# BLDC.net
KiCad netlist of a schematic drawn in Altium Designer
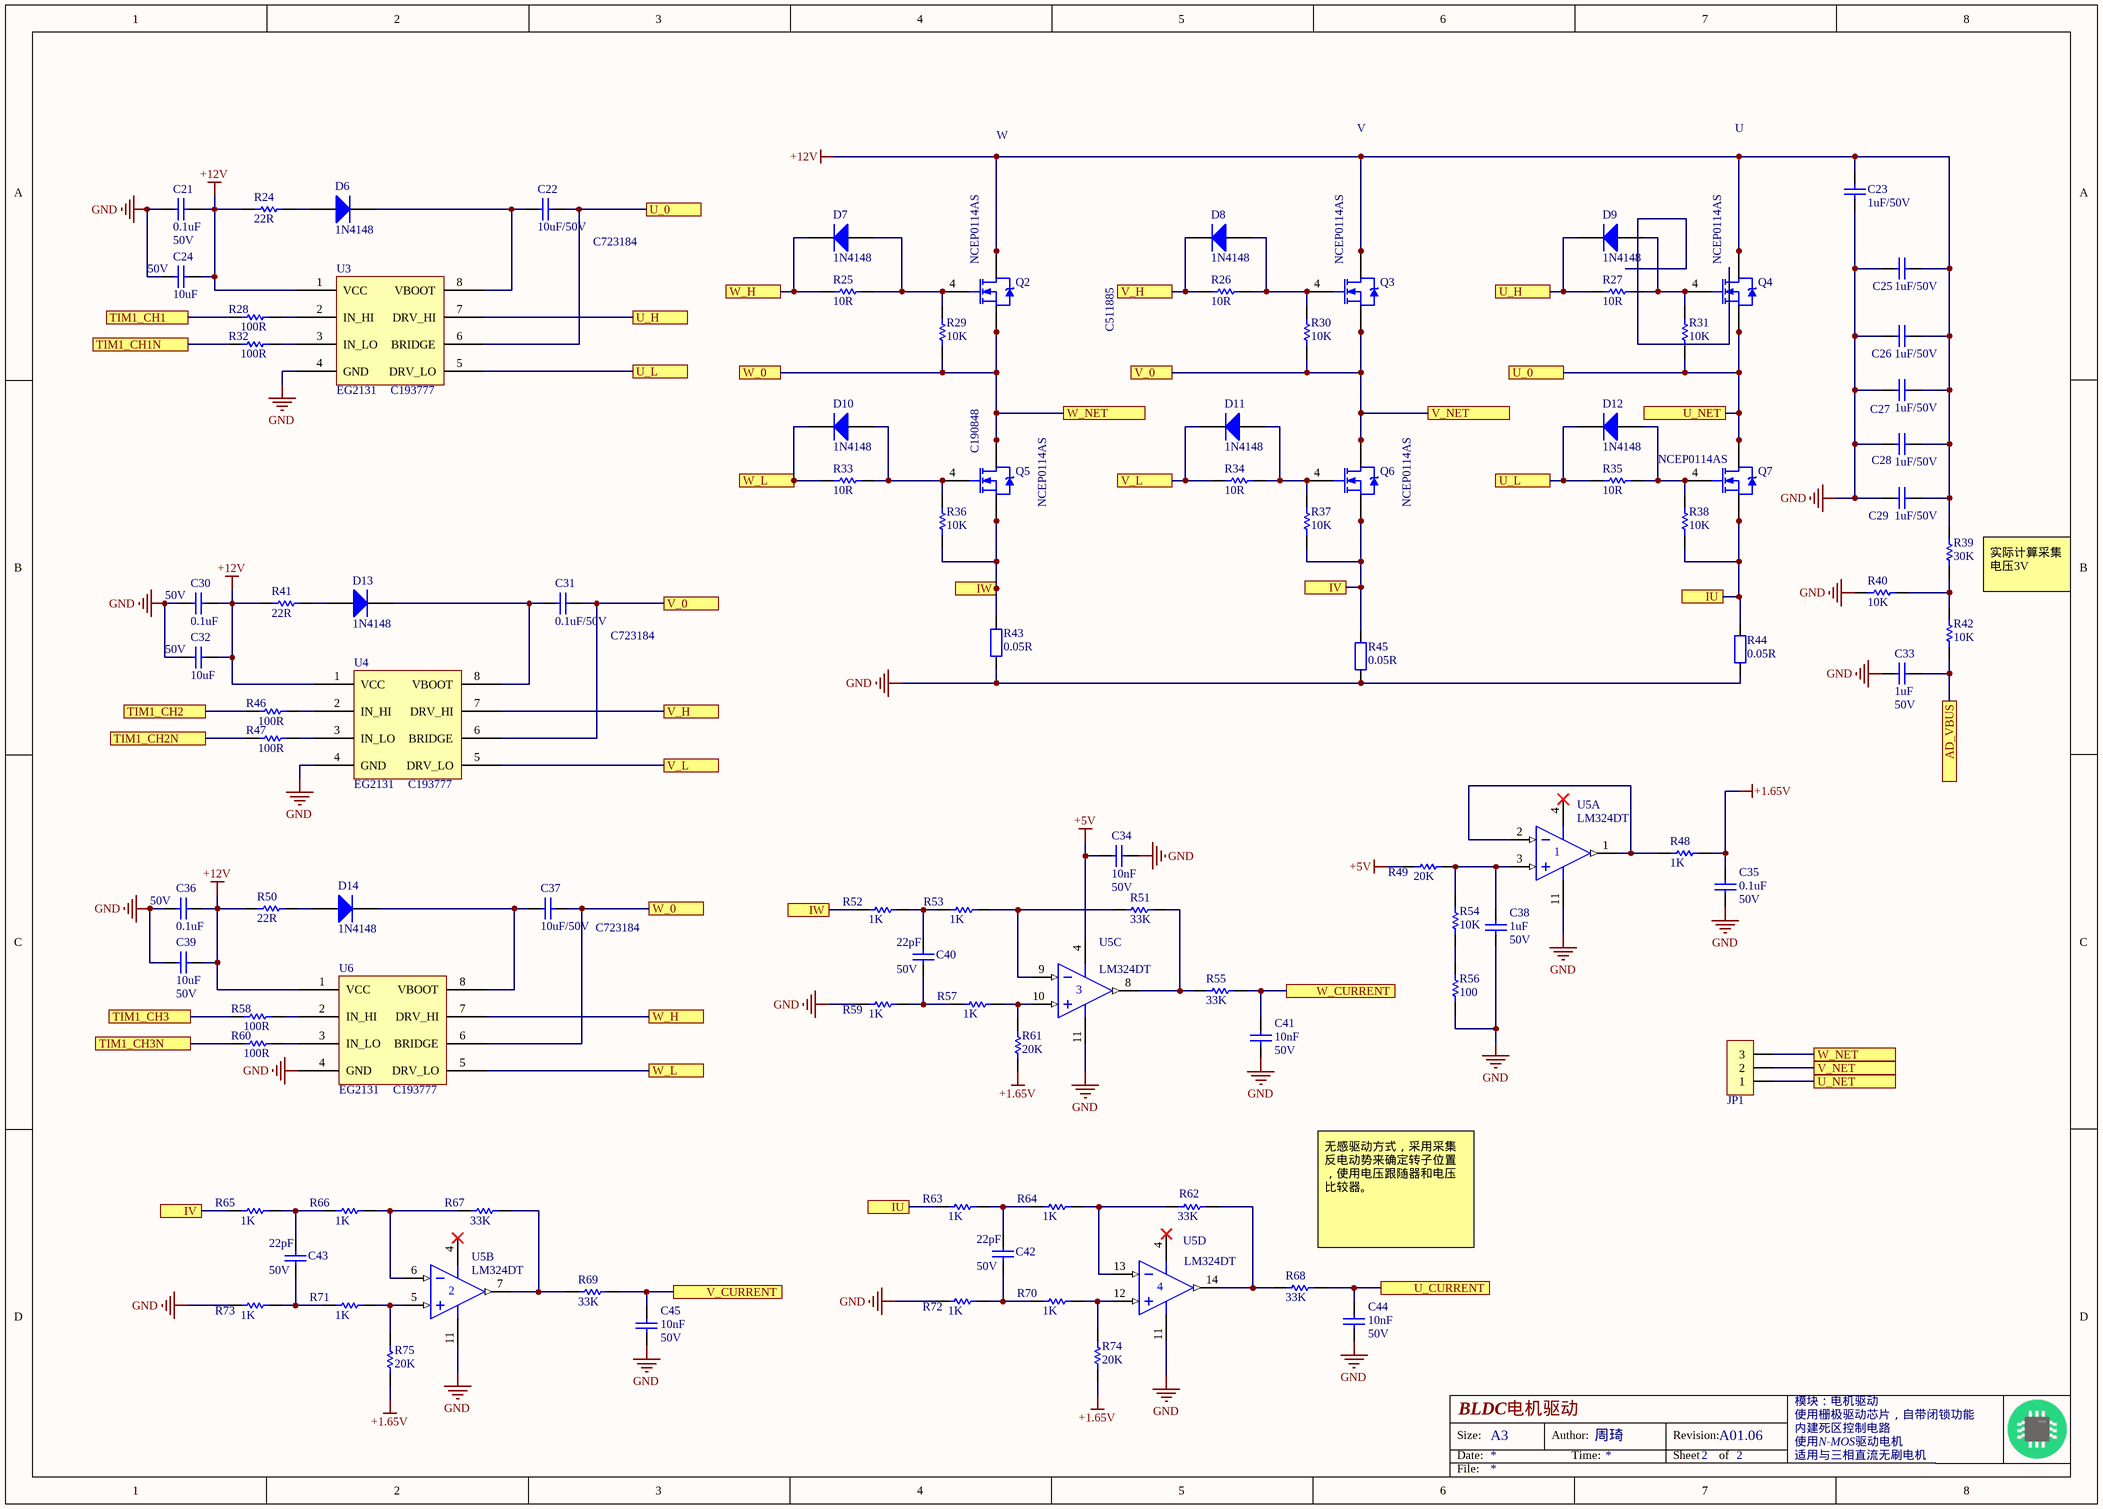
[diagram p0: BLDC.SchDoc]

(export (version "E")
  (design (tool "Eeschema 10.0.6"))
  (components
    (comp (ref "C21")
      (value "0.1uF")
      (footprint "C0603_L")
      (fields (field (name "PARM") "50V"))
      (libsource (lib "Miscellaneous Devices") (part "Cap"))
    )
    (comp (ref "C22")
      (value "10uF/50V")
      (footprint "C0603_L")
      (description "C89632")
      (libsource (lib "Miscellaneous Devices") (part "Cap"))
    )
    (comp (ref "C23")
      (value "1uF/50V")
      (footprint "C1210_L")
      (libsource (lib "Miscellaneous Devices") (part "Cap"))
    )
    (comp (ref "C24")
      (value "10uF")
      (footprint "C0805_L")
      (fields (field (name "PARM") "50V"))
      (libsource (lib "Miscellaneous Devices") (part "Cap"))
    )
    (comp (ref "C25")
      (value "1uF/50V")
      (footprint "C1210_L")
      (libsource (lib "Miscellaneous Devices") (part "Cap"))
    )
    (comp (ref "C26")
      (value "1uF/50V")
      (footprint "C1210_L")
      (libsource (lib "Miscellaneous Devices") (part "Cap"))
    )
    (comp (ref "C27")
      (value "1uF/50V")
      (footprint "C1210_L")
      (libsource (lib "Miscellaneous Devices") (part "Cap"))
    )
    (comp (ref "C28")
      (value "1uF/50V")
      (footprint "C1210_L")
      (libsource (lib "Miscellaneous Devices") (part "Cap"))
    )
    (comp (ref "C29")
      (value "1uF/50V")
      (footprint "C1210_L")
      (libsource (lib "Miscellaneous Devices") (part "Cap"))
    )
    (comp (ref "C30")
      (value "0.1uF")
      (footprint "C0603_L")
      (fields (field (name "PARM") "50V"))
      (libsource (lib "Miscellaneous Devices") (part "Cap"))
    )
    (comp (ref "C31")
      (value "0.1uF/50V")
      (footprint "C0603_L")
      (description "C89632")
      (libsource (lib "Miscellaneous Devices") (part "Cap"))
    )
    (comp (ref "C32")
      (value "10uF")
      (footprint "C0805_L")
      (fields (field (name "PARM") "50V"))
      (libsource (lib "Miscellaneous Devices") (part "Cap"))
    )
    (comp (ref "C33")
      (value "1uF")
      (footprint "C0603_L")
      (fields (field (name "PARM") "50V"))
      (libsource (lib "Miscellaneous Devices") (part "Cap"))
    )
    (comp (ref "C34")
      (value "10nF")
      (footprint "C0603_L")
      (fields (field (name "PARM") "50V"))
      (libsource (lib "Miscellaneous Devices") (part "Cap"))
    )
    (comp (ref "C35")
      (value "0.1uF")
      (footprint "C0603_L")
      (fields (field (name "PARM") "50V"))
      (libsource (lib "Miscellaneous Devices") (part "Cap"))
    )
    (comp (ref "C36")
      (value "0.1uF")
      (footprint "C0603_L")
      (fields (field (name "PARM") "50V"))
      (libsource (lib "Miscellaneous Devices") (part "Cap"))
    )
    (comp (ref "C37")
      (value "10uF/50V")
      (footprint "C0603_L")
      (description "C89632")
      (libsource (lib "Miscellaneous Devices") (part "Cap"))
    )
    (comp (ref "C38")
      (value "1uF")
      (footprint "C0603_L")
      (fields (field (name "PARM") "50V"))
      (libsource (lib "Miscellaneous Devices") (part "Cap"))
    )
    (comp (ref "C39")
      (value "10uF")
      (footprint "C0805_L")
      (fields (field (name "PARM") "50V"))
      (libsource (lib "Miscellaneous Devices") (part "Cap"))
    )
    (comp (ref "C40")
      (value "22pF")
      (footprint "C0603_L")
      (fields (field (name "PARM") "50V"))
      (libsource (lib "Miscellaneous Devices") (part "Cap"))
    )
    (comp (ref "C41")
      (value "10nF")
      (footprint "C0603_L")
      (fields (field (name "PARM") "50V"))
      (libsource (lib "Miscellaneous Devices") (part "Cap"))
    )
    (comp (ref "C42")
      (value "22pF")
      (footprint "C0603_L")
      (fields (field (name "PARM") "50V"))
      (libsource (lib "Miscellaneous Devices") (part "Cap"))
    )
    (comp (ref "C43")
      (value "22pF")
      (footprint "C0603_L")
      (fields (field (name "PARM") "50V"))
      (libsource (lib "Miscellaneous Devices") (part "Cap"))
    )
    (comp (ref "C44")
      (value "10nF")
      (footprint "C0603_L")
      (fields (field (name "PARM") "50V"))
      (libsource (lib "Miscellaneous Devices") (part "Cap"))
    )
    (comp (ref "C45")
      (value "10nF")
      (footprint "C0603_L")
      (fields (field (name "PARM") "50V"))
      (libsource (lib "Miscellaneous Devices") (part "Cap"))
    )
    (comp (ref "D6")
      (value "1N4148")
      (footprint "SOD-123")
      (description "二极管")
      (libsource (lib "Miscellaneous Devices LC") (part "SOD-323 1N4148WS T4"))
    )
    (comp (ref "D7")
      (value "1N4148")
      (footprint "SOD-123")
      (description "二极管")
      (libsource (lib "Miscellaneous Devices LC") (part "SOD-323 1N4148WS T4"))
    )
    (comp (ref "D8")
      (value "1N4148")
      (footprint "SOD-123")
      (description "二极管")
      (libsource (lib "Miscellaneous Devices LC") (part "SOD-323 1N4148WS T4"))
    )
    (comp (ref "D9")
      (value "1N4148")
      (footprint "SOD-123")
      (description "二极管")
      (libsource (lib "Miscellaneous Devices LC") (part "SOD-323 1N4148WS T4"))
    )
    (comp (ref "D10")
      (value "1N4148")
      (footprint "SOD-123")
      (description "二极管")
      (libsource (lib "Miscellaneous Devices LC") (part "SOD-323 1N4148WS T4"))
    )
    (comp (ref "D11")
      (value "1N4148")
      (footprint "SOD-123")
      (description "二极管")
      (libsource (lib "Miscellaneous Devices LC") (part "SOD-323 1N4148WS T4"))
    )
    (comp (ref "D12")
      (value "1N4148")
      (footprint "SOD-123")
      (description "二极管")
      (libsource (lib "Miscellaneous Devices LC") (part "SOD-323 1N4148WS T4"))
    )
    (comp (ref "D13")
      (value "1N4148")
      (footprint "SOD-123")
      (description "二极管")
      (libsource (lib "Miscellaneous Devices LC") (part "SOD-323 1N4148WS T4"))
    )
    (comp (ref "D14")
      (value "1N4148")
      (footprint "SOD-123")
      (description "二极管")
      (libsource (lib "Miscellaneous Devices LC") (part "SOD-323 1N4148WS T4"))
    )
    (comp (ref "JP1")
      (value "HDR-1X3")
      (footprint "KF350-3P")
      (description "3P接插件")
      (fields (field (name "版权归属") "源创客"))
      (libsource (lib "接插件") (part "Header 3"))
    )
    (comp (ref "Q2")
      (value "NCEP0114AS")
      (footprint "SOP8")
      (description "C190848")
      (fields (field (name "PUBLISHER") "60V"))
      (libsource (lib "Miscellaneous Devices") (part "NMOS-2"))
    )
    (comp (ref "Q3")
      (value "NCEP0114AS")
      (footprint "SOP8")
      (description "C190848")
      (fields (field (name "PUBLISHER") "60V"))
      (libsource (lib "Miscellaneous Devices") (part "NMOS-2"))
    )
    (comp (ref "Q4")
      (value "NCEP0114AS")
      (footprint "SOP8")
      (description "C190848")
      (fields (field (name "PUBLISHER") "60V"))
      (libsource (lib "Miscellaneous Devices") (part "NMOS-2"))
    )
    (comp (ref "Q5")
      (value "NCEP0114AS")
      (footprint "SOP8")
      (description "C190848")
      (fields (field (name "PUBLISHER") "60V"))
      (libsource (lib "Miscellaneous Devices") (part "NMOS-2"))
    )
    (comp (ref "Q6")
      (value "NCEP0114AS")
      (footprint "SOP8")
      (description "C190848")
      (fields (field (name "PUBLISHER") "60V"))
      (libsource (lib "Miscellaneous Devices") (part "NMOS-2"))
    )
    (comp (ref "Q7")
      (value "NCEP0114AS")
      (footprint "SOP8")
      (description "C190848")
      (fields (field (name "PUBLISHER") "60V"))
      (libsource (lib "Miscellaneous Devices") (part "NMOS-2"))
    )
    (comp (ref "R24")
      (value "22R")
      (footprint "R0603_L")
      (description "Resistor")
      (libsource (lib "Miscellaneous Devices") (part "Res1"))
    )
    (comp (ref "R25")
      (value "10R")
      (footprint "R0603_L")
      (description "Resistor")
      (libsource (lib "Miscellaneous Devices") (part "Res1"))
    )
    (comp (ref "R26")
      (value "10R")
      (footprint "R0603_L")
      (description "Resistor")
      (libsource (lib "Miscellaneous Devices") (part "Res1"))
    )
    (comp (ref "R27")
      (value "10R")
      (footprint "R0603_L")
      (description "Resistor")
      (libsource (lib "Miscellaneous Devices") (part "Res1"))
    )
    (comp (ref "R28")
      (value "100R")
      (footprint "R0603_L")
      (description "Resistor")
      (libsource (lib "Miscellaneous Devices") (part "Res1"))
    )
    (comp (ref "R29")
      (value "10K")
      (footprint "R0603_L")
      (description "Resistor")
      (libsource (lib "Miscellaneous Devices") (part "Res1"))
    )
    (comp (ref "R30")
      (value "10K")
      (footprint "R0603_L")
      (description "Resistor")
      (libsource (lib "Miscellaneous Devices") (part "Res1"))
    )
    (comp (ref "R31")
      (value "10K")
      (footprint "R0603_L")
      (description "Resistor")
      (libsource (lib "Miscellaneous Devices") (part "Res1"))
    )
    (comp (ref "R32")
      (value "100R")
      (footprint "R0603_L")
      (description "Resistor")
      (libsource (lib "Miscellaneous Devices") (part "Res1"))
    )
    (comp (ref "R33")
      (value "10R")
      (footprint "R0603_L")
      (description "Resistor")
      (libsource (lib "Miscellaneous Devices") (part "Res1"))
    )
    (comp (ref "R34")
      (value "10R")
      (footprint "R0603_L")
      (description "Resistor")
      (libsource (lib "Miscellaneous Devices") (part "Res1"))
    )
    (comp (ref "R35")
      (value "10R")
      (footprint "R0603_L")
      (description "Resistor")
      (libsource (lib "Miscellaneous Devices") (part "Res1"))
    )
    (comp (ref "R36")
      (value "10K")
      (footprint "R0603_L")
      (description "Resistor")
      (libsource (lib "Miscellaneous Devices") (part "Res1"))
    )
    (comp (ref "R37")
      (value "10K")
      (footprint "R0603_L")
      (description "Resistor")
      (libsource (lib "Miscellaneous Devices") (part "Res1"))
    )
    (comp (ref "R38")
      (value "10K")
      (footprint "R0603_L")
      (description "Resistor")
      (libsource (lib "Miscellaneous Devices") (part "Res1"))
    )
    (comp (ref "R39")
      (value "30K")
      (footprint "R0603_L")
      (description "Resistor")
      (libsource (lib "Miscellaneous Devices") (part "Res1"))
    )
    (comp (ref "R40")
      (value "10K")
      (footprint "R0603_L")
      (description "Resistor")
      (libsource (lib "Miscellaneous Devices") (part "Res1"))
    )
    (comp (ref "R41")
      (value "22R")
      (footprint "R0603_L")
      (description "Resistor")
      (libsource (lib "Miscellaneous Devices") (part "Res1"))
    )
    (comp (ref "R42")
      (value "10K")
      (footprint "R0603_L")
      (description "Resistor")
      (libsource (lib "Miscellaneous Devices") (part "Res1"))
    )
    (comp (ref "R43")
      (value "0.05R")
      (footprint "R2512_L")
      (description "电流检测电阻")
      (fields (field (name "版权归属") "源创客"))
      (libsource (lib "电阻-电容-电感") (part "R-I"))
    )
    (comp (ref "R44")
      (value "0.05R")
      (footprint "R2512_L")
      (description "电流检测电阻")
      (fields (field (name "版权归属") "源创客"))
      (libsource (lib "电阻-电容-电感") (part "R-I"))
    )
    (comp (ref "R45")
      (value "0.05R")
      (footprint "R2512_L")
      (description "电流检测电阻")
      (fields (field (name "版权归属") "源创客"))
      (libsource (lib "电阻-电容-电感") (part "R-I"))
    )
    (comp (ref "R46")
      (value "100R")
      (footprint "R0603_L")
      (description "Resistor")
      (libsource (lib "Miscellaneous Devices") (part "Res1"))
    )
    (comp (ref "R47")
      (value "100R")
      (footprint "R0603_L")
      (description "Resistor")
      (libsource (lib "Miscellaneous Devices") (part "Res1"))
    )
    (comp (ref "R48")
      (value "1K")
      (footprint "R0603_L")
      (description "Resistor")
      (libsource (lib "Miscellaneous Devices") (part "Res1"))
    )
    (comp (ref "R49")
      (value "20K")
      (footprint "R0603_L")
      (description "Resistor")
      (libsource (lib "Miscellaneous Devices") (part "Res1"))
    )
    (comp (ref "R50")
      (value "22R")
      (footprint "R0603_L")
      (description "Resistor")
      (libsource (lib "Miscellaneous Devices") (part "Res1"))
    )
    (comp (ref "R51")
      (value "33K")
      (footprint "R0603_L")
      (description "Resistor")
      (libsource (lib "Miscellaneous Devices") (part "Res1"))
    )
    (comp (ref "R52")
      (value "1K")
      (footprint "R0603_L")
      (description "Resistor")
      (libsource (lib "Miscellaneous Devices") (part "Res1"))
    )
    (comp (ref "R53")
      (value "1K")
      (footprint "R0603_L")
      (description "Resistor")
      (libsource (lib "Miscellaneous Devices") (part "Res1"))
    )
    (comp (ref "R54")
      (value "10K")
      (footprint "R0603_L")
      (description "Resistor")
      (libsource (lib "Miscellaneous Devices") (part "Res1"))
    )
    (comp (ref "R55")
      (value "33K")
      (footprint "R0603_L")
      (description "Resistor")
      (libsource (lib "Miscellaneous Devices") (part "Res1"))
    )
    (comp (ref "R56")
      (value "100")
      (footprint "R0603_L")
      (description "Resistor")
      (libsource (lib "Miscellaneous Devices") (part "Res1"))
    )
    (comp (ref "R57")
      (value "1K")
      (footprint "R0603_L")
      (description "Resistor")
      (libsource (lib "Miscellaneous Devices") (part "Res1"))
    )
    (comp (ref "R58")
      (value "100R")
      (footprint "R0603_L")
      (description "Resistor")
      (libsource (lib "Miscellaneous Devices") (part "Res1"))
    )
    (comp (ref "R59")
      (value "1K")
      (footprint "R0603_L")
      (description "Resistor")
      (libsource (lib "Miscellaneous Devices") (part "Res1"))
    )
    (comp (ref "R60")
      (value "100R")
      (footprint "R0603_L")
      (description "Resistor")
      (libsource (lib "Miscellaneous Devices") (part "Res1"))
    )
    (comp (ref "R61")
      (value "20K")
      (footprint "R0603_L")
      (description "Resistor")
      (libsource (lib "Miscellaneous Devices") (part "Res1"))
    )
    (comp (ref "R62")
      (value "33K")
      (footprint "R0603_L")
      (description "Resistor")
      (libsource (lib "Miscellaneous Devices") (part "Res1"))
    )
    (comp (ref "R63")
      (value "1K")
      (footprint "R0603_L")
      (description "Resistor")
      (libsource (lib "Miscellaneous Devices") (part "Res1"))
    )
    (comp (ref "R64")
      (value "1K")
      (footprint "R0603_L")
      (description "Resistor")
      (libsource (lib "Miscellaneous Devices") (part "Res1"))
    )
    (comp (ref "R65")
      (value "1K")
      (footprint "R0603_L")
      (description "Resistor")
      (libsource (lib "Miscellaneous Devices") (part "Res1"))
    )
    (comp (ref "R66")
      (value "1K")
      (footprint "R0603_L")
      (description "Resistor")
      (libsource (lib "Miscellaneous Devices") (part "Res1"))
    )
    (comp (ref "R67")
      (value "33K")
      (footprint "R0603_L")
      (description "Resistor")
      (libsource (lib "Miscellaneous Devices") (part "Res1"))
    )
    (comp (ref "R68")
      (value "33K")
      (footprint "R0603_L")
      (description "Resistor")
      (libsource (lib "Miscellaneous Devices") (part "Res1"))
    )
    (comp (ref "R69")
      (value "33K")
      (footprint "R0603_L")
      (description "Resistor")
      (libsource (lib "Miscellaneous Devices") (part "Res1"))
    )
    (comp (ref "R70")
      (value "1K")
      (footprint "R0603_L")
      (description "Resistor")
      (libsource (lib "Miscellaneous Devices") (part "Res1"))
    )
    (comp (ref "R71")
      (value "1K")
      (footprint "R0603_L")
      (description "Resistor")
      (libsource (lib "Miscellaneous Devices") (part "Res1"))
    )
    (comp (ref "R72")
      (value "1K")
      (footprint "R0603_L")
      (description "Resistor")
      (libsource (lib "Miscellaneous Devices") (part "Res1"))
    )
    (comp (ref "R73")
      (value "1K")
      (footprint "R0603_L")
      (description "Resistor")
      (libsource (lib "Miscellaneous Devices") (part "Res1"))
    )
    (comp (ref "R74")
      (value "20K")
      (footprint "R0603_L")
      (description "Resistor")
      (libsource (lib "Miscellaneous Devices") (part "Res1"))
    )
    (comp (ref "R75")
      (value "20K")
      (footprint "R0603_L")
      (description "Resistor")
      (libsource (lib "Miscellaneous Devices") (part "Res1"))
    )
    (comp (ref "U3")
      (value "EG2131")
      (footprint "SOP8")
      (description "C193777")
      (fields (field (name "编号") "C193777"))
      (libsource (lib "Tang") (part "NCP5106BDR2G"))
    )
    (comp (ref "U4")
      (value "EG2131")
      (footprint "SOP8")
      (description "C193777")
      (fields (field (name "编号") "C193777"))
      (libsource (lib "Tang") (part "NCP5106BDR2G"))
    )
    (comp (ref "U5")
      (value "LM324DT")
      (footprint "SOIC-14")
      (description "运放")
      (libsource (lib "Miscellaneous Devices LC") (part "LM324DT_[C71035]"))
    )
    (comp (ref "U6")
      (value "EG2131")
      (footprint "SOP8")
      (description "C193777")
      (fields (field (name "编号") "C193777"))
      (libsource (lib "Tang") (part "NCP5106BDR2G"))
    )
  )
  (nets
    (net (code "1") (name "+1.65V") (class "Default")
      (node (ref "C35") (pin "2") (pinfunction "2_2") (pintype "passive"))
      (node (ref "R48") (pin "1") (pinfunction "1_1") (pintype "passive"))
      (node (ref "R61") (pin "1") (pinfunction "1_1") (pintype "passive"))
      (node (ref "R74") (pin "1") (pinfunction "1_1") (pintype "passive"))
      (node (ref "R75") (pin "1") (pinfunction "1_1") (pintype "passive"))
    )
    (net (code "2") (name "+5V") (class "Default")
      (node (ref "C34") (pin "2") (pinfunction "2_2") (pintype "passive"))
      (node (ref "R49") (pin "1") (pinfunction "1_1") (pintype "passive"))
      (node (ref "U5") (pin "4") (pinfunction "V+_4") (pintype "power_in"))
    )
    (net (code "3") (name "+12V") (class "Default")
      (node (ref "C21") (pin "1") (pinfunction "1_1") (pintype "passive"))
      (node (ref "C23") (pin "1") (pinfunction "1_1") (pintype "passive"))
      (node (ref "C24") (pin "1") (pinfunction "1_1") (pintype "passive"))
      (node (ref "C25") (pin "1") (pinfunction "1_1") (pintype "passive"))
      (node (ref "C26") (pin "1") (pinfunction "1_1") (pintype "passive"))
      (node (ref "C27") (pin "1") (pinfunction "1_1") (pintype "passive"))
      (node (ref "C28") (pin "1") (pinfunction "1_1") (pintype "passive"))
      (node (ref "C29") (pin "1") (pinfunction "1_1") (pintype "passive"))
      (node (ref "C30") (pin "1") (pinfunction "1_1") (pintype "passive"))
      (node (ref "C32") (pin "1") (pinfunction "1_1") (pintype "passive"))
      (node (ref "C36") (pin "1") (pinfunction "1_1") (pintype "passive"))
      (node (ref "C39") (pin "1") (pinfunction "1_1") (pintype "passive"))
      (node (ref "Q2") (pin "5") (pinfunction "D_5") (pintype "passive"))
      (node (ref "Q2") (pin "6") (pinfunction "D_6") (pintype "passive"))
      (node (ref "Q2") (pin "7") (pinfunction "D_7") (pintype "passive"))
      (node (ref "Q2") (pin "8") (pinfunction "D_8") (pintype "passive"))
      (node (ref "Q3") (pin "5") (pinfunction "D_5") (pintype "passive"))
      (node (ref "Q3") (pin "6") (pinfunction "D_6") (pintype "passive"))
      (node (ref "Q3") (pin "7") (pinfunction "D_7") (pintype "passive"))
      (node (ref "Q3") (pin "8") (pinfunction "D_8") (pintype "passive"))
      (node (ref "Q4") (pin "5") (pinfunction "D_5") (pintype "passive"))
      (node (ref "Q4") (pin "6") (pinfunction "D_6") (pintype "passive"))
      (node (ref "Q4") (pin "7") (pinfunction "D_7") (pintype "passive"))
      (node (ref "Q4") (pin "8") (pinfunction "D_8") (pintype "passive"))
      (node (ref "R24") (pin "1") (pinfunction "1_1") (pintype "passive"))
      (node (ref "R39") (pin "2") (pinfunction "2_2") (pintype "passive"))
      (node (ref "R41") (pin "1") (pinfunction "1_1") (pintype "passive"))
      (node (ref "R50") (pin "1") (pinfunction "1_1") (pintype "passive"))
      (node (ref "U3") (pin "1") (pinfunction "VCC_1") (pintype "passive"))
      (node (ref "U4") (pin "1") (pinfunction "VCC_1") (pintype "passive"))
      (node (ref "U6") (pin "1") (pinfunction "VCC_1") (pintype "passive"))
    )
    (net (code "4") (name "/AD_VBUS") (class "Default")
      (node (ref "C33") (pin "2") (pinfunction "2_2") (pintype "passive"))
      (node (ref "R42") (pin "2") (pinfunction "2_2") (pintype "passive"))
    )
    (net (code "5") (name "/IU") (class "Default")
      (node (ref "Q7") (pin "1") (pinfunction "S_1") (pintype "passive"))
      (node (ref "Q7") (pin "2") (pinfunction "S_2") (pintype "passive"))
      (node (ref "Q7") (pin "3") (pinfunction "S_3") (pintype "passive"))
      (node (ref "R38") (pin "1") (pinfunction "1_1") (pintype "passive"))
      (node (ref "R44") (pin "2") (pinfunction "2_2") (pintype "passive"))
      (node (ref "R63") (pin "1") (pinfunction "1_1") (pintype "passive"))
    )
    (net (code "6") (name "/IV") (class "Default")
      (node (ref "Q6") (pin "1") (pinfunction "S_1") (pintype "passive"))
      (node (ref "Q6") (pin "2") (pinfunction "S_2") (pintype "passive"))
      (node (ref "Q6") (pin "3") (pinfunction "S_3") (pintype "passive"))
      (node (ref "R37") (pin "1") (pinfunction "1_1") (pintype "passive"))
      (node (ref "R45") (pin "2") (pinfunction "2_2") (pintype "passive"))
      (node (ref "R65") (pin "1") (pinfunction "1_1") (pintype "passive"))
    )
    (net (code "7") (name "/IW") (class "Default")
      (node (ref "Q5") (pin "1") (pinfunction "S_1") (pintype "passive"))
      (node (ref "Q5") (pin "2") (pinfunction "S_2") (pintype "passive"))
      (node (ref "Q5") (pin "3") (pinfunction "S_3") (pintype "passive"))
      (node (ref "R36") (pin "1") (pinfunction "1_1") (pintype "passive"))
      (node (ref "R43") (pin "2") (pinfunction "2_2") (pintype "passive"))
      (node (ref "R52") (pin "1") (pinfunction "1_1") (pintype "passive"))
    )
    (net (code "8") (name "/TIM1_CH1") (class "Default")
      (node (ref "R28") (pin "1") (pinfunction "1_1") (pintype "passive"))
    )
    (net (code "9") (name "/TIM1_CH1N") (class "Default")
      (node (ref "R32") (pin "1") (pinfunction "1_1") (pintype "passive"))
    )
    (net (code "10") (name "/TIM1_CH2") (class "Default")
      (node (ref "R46") (pin "1") (pinfunction "1_1") (pintype "passive"))
    )
    (net (code "11") (name "/TIM1_CH2N") (class "Default")
      (node (ref "R47") (pin "1") (pinfunction "1_1") (pintype "passive"))
    )
    (net (code "12") (name "/TIM1_CH3") (class "Default")
      (node (ref "R58") (pin "1") (pinfunction "1_1") (pintype "passive"))
    )
    (net (code "13") (name "/TIM1_CH3N") (class "Default")
      (node (ref "R60") (pin "1") (pinfunction "1_1") (pintype "passive"))
    )
    (net (code "14") (name "/U_0") (class "Default")
      (node (ref "C22") (pin "1") (pinfunction "1_1") (pintype "passive"))
      (node (ref "JP1") (pin "1") (pinfunction "1_1") (pintype "passive"))
      (node (ref "Q4") (pin "1") (pinfunction "S_1") (pintype "passive"))
      (node (ref "Q4") (pin "2") (pinfunction "S_2") (pintype "passive"))
      (node (ref "Q4") (pin "3") (pinfunction "S_3") (pintype "passive"))
      (node (ref "Q7") (pin "5") (pinfunction "D_5") (pintype "passive"))
      (node (ref "Q7") (pin "6") (pinfunction "D_6") (pintype "passive"))
      (node (ref "Q7") (pin "7") (pinfunction "D_7") (pintype "passive"))
      (node (ref "Q7") (pin "8") (pinfunction "D_8") (pintype "passive"))
      (node (ref "R31") (pin "1") (pinfunction "1_1") (pintype "passive"))
      (node (ref "U3") (pin "6") (pinfunction "BRIDGE_6") (pintype "passive"))
    )
    (net (code "15") (name "/U_CURRENT") (class "Default")
      (node (ref "C44") (pin "2") (pinfunction "2_2") (pintype "passive"))
      (node (ref "R68") (pin "1") (pinfunction "1_1") (pintype "passive"))
    )
    (net (code "16") (name "/U_H") (class "Default")
      (node (ref "D9") (pin "2") (pinfunction "K_2") (pintype "passive"))
      (node (ref "R27") (pin "1") (pinfunction "1_1") (pintype "passive"))
      (node (ref "U3") (pin "7") (pinfunction "DRV_HI_7") (pintype "passive"))
    )
    (net (code "17") (name "/U_L") (class "Default")
      (node (ref "D12") (pin "2") (pinfunction "K_2") (pintype "passive"))
      (node (ref "R35") (pin "1") (pinfunction "1_1") (pintype "passive"))
      (node (ref "U3") (pin "5") (pinfunction "DRV_LO_5") (pintype "passive"))
    )
    (net (code "18") (name "/V_0") (class "Default")
      (node (ref "C31") (pin "1") (pinfunction "1_1") (pintype "passive"))
      (node (ref "JP1") (pin "2") (pinfunction "2_2") (pintype "passive"))
      (node (ref "Q3") (pin "1") (pinfunction "S_1") (pintype "passive"))
      (node (ref "Q3") (pin "2") (pinfunction "S_2") (pintype "passive"))
      (node (ref "Q3") (pin "3") (pinfunction "S_3") (pintype "passive"))
      (node (ref "Q6") (pin "5") (pinfunction "D_5") (pintype "passive"))
      (node (ref "Q6") (pin "6") (pinfunction "D_6") (pintype "passive"))
      (node (ref "Q6") (pin "7") (pinfunction "D_7") (pintype "passive"))
      (node (ref "Q6") (pin "8") (pinfunction "D_8") (pintype "passive"))
      (node (ref "R30") (pin "1") (pinfunction "1_1") (pintype "passive"))
      (node (ref "U4") (pin "6") (pinfunction "BRIDGE_6") (pintype "passive"))
    )
    (net (code "19") (name "/V_CURRENT") (class "Default")
      (node (ref "C45") (pin "2") (pinfunction "2_2") (pintype "passive"))
      (node (ref "R69") (pin "1") (pinfunction "1_1") (pintype "passive"))
    )
    (net (code "20") (name "/V_H") (class "Default")
      (node (ref "D8") (pin "2") (pinfunction "K_2") (pintype "passive"))
      (node (ref "R26") (pin "1") (pinfunction "1_1") (pintype "passive"))
      (node (ref "U4") (pin "7") (pinfunction "DRV_HI_7") (pintype "passive"))
    )
    (net (code "21") (name "/V_L") (class "Default")
      (node (ref "D11") (pin "2") (pinfunction "K_2") (pintype "passive"))
      (node (ref "R34") (pin "1") (pinfunction "1_1") (pintype "passive"))
      (node (ref "U4") (pin "5") (pinfunction "DRV_LO_5") (pintype "passive"))
    )
    (net (code "22") (name "/W_0") (class "Default")
      (node (ref "C37") (pin "1") (pinfunction "1_1") (pintype "passive"))
      (node (ref "JP1") (pin "3") (pinfunction "3_3") (pintype "passive"))
      (node (ref "Q2") (pin "1") (pinfunction "S_1") (pintype "passive"))
      (node (ref "Q2") (pin "2") (pinfunction "S_2") (pintype "passive"))
      (node (ref "Q2") (pin "3") (pinfunction "S_3") (pintype "passive"))
      (node (ref "Q5") (pin "5") (pinfunction "D_5") (pintype "passive"))
      (node (ref "Q5") (pin "6") (pinfunction "D_6") (pintype "passive"))
      (node (ref "Q5") (pin "7") (pinfunction "D_7") (pintype "passive"))
      (node (ref "Q5") (pin "8") (pinfunction "D_8") (pintype "passive"))
      (node (ref "R29") (pin "1") (pinfunction "1_1") (pintype "passive"))
      (node (ref "U6") (pin "6") (pinfunction "BRIDGE_6") (pintype "passive"))
    )
    (net (code "23") (name "/W_CURRENT") (class "Default")
      (node (ref "C41") (pin "2") (pinfunction "2_2") (pintype "passive"))
      (node (ref "R55") (pin "1") (pinfunction "1_1") (pintype "passive"))
    )
    (net (code "24") (name "/W_H") (class "Default")
      (node (ref "D7") (pin "2") (pinfunction "K_2") (pintype "passive"))
      (node (ref "R25") (pin "1") (pinfunction "1_1") (pintype "passive"))
      (node (ref "U6") (pin "7") (pinfunction "DRV_HI_7") (pintype "passive"))
    )
    (net (code "25") (name "/W_L") (class "Default")
      (node (ref "D10") (pin "2") (pinfunction "K_2") (pintype "passive"))
      (node (ref "R33") (pin "1") (pinfunction "1_1") (pintype "passive"))
      (node (ref "U6") (pin "5") (pinfunction "DRV_LO_5") (pintype "passive"))
    )
    (net (code "26") (name "GND") (class "Default")
      (node (ref "C21") (pin "2") (pinfunction "2_2") (pintype "passive"))
      (node (ref "C23") (pin "2") (pinfunction "2_2") (pintype "passive"))
      (node (ref "C24") (pin "2") (pinfunction "2_2") (pintype "passive"))
      (node (ref "C25") (pin "2") (pinfunction "2_2") (pintype "passive"))
      (node (ref "C26") (pin "2") (pinfunction "2_2") (pintype "passive"))
      (node (ref "C27") (pin "2") (pinfunction "2_2") (pintype "passive"))
      (node (ref "C28") (pin "2") (pinfunction "2_2") (pintype "passive"))
      (node (ref "C29") (pin "2") (pinfunction "2_2") (pintype "passive"))
      (node (ref "C30") (pin "2") (pinfunction "2_2") (pintype "passive"))
      (node (ref "C32") (pin "2") (pinfunction "2_2") (pintype "passive"))
      (node (ref "C33") (pin "1") (pinfunction "1_1") (pintype "passive"))
      (node (ref "C34") (pin "1") (pinfunction "1_1") (pintype "passive"))
      (node (ref "C35") (pin "1") (pinfunction "1_1") (pintype "passive"))
      (node (ref "C36") (pin "2") (pinfunction "2_2") (pintype "passive"))
      (node (ref "C38") (pin "1") (pinfunction "1_1") (pintype "passive"))
      (node (ref "C39") (pin "2") (pinfunction "2_2") (pintype "passive"))
      (node (ref "C41") (pin "1") (pinfunction "1_1") (pintype "passive"))
      (node (ref "C44") (pin "1") (pinfunction "1_1") (pintype "passive"))
      (node (ref "C45") (pin "1") (pinfunction "1_1") (pintype "passive"))
      (node (ref "R40") (pin "2") (pinfunction "2_2") (pintype "passive"))
      (node (ref "R43") (pin "1") (pinfunction "1_1") (pintype "passive"))
      (node (ref "R44") (pin "1") (pinfunction "1_1") (pintype "passive"))
      (node (ref "R45") (pin "1") (pinfunction "1_1") (pintype "passive"))
      (node (ref "R56") (pin "1") (pinfunction "1_1") (pintype "passive"))
      (node (ref "R59") (pin "1") (pinfunction "1_1") (pintype "passive"))
      (node (ref "R72") (pin "1") (pinfunction "1_1") (pintype "passive"))
      (node (ref "R73") (pin "1") (pinfunction "1_1") (pintype "passive"))
      (node (ref "U3") (pin "4") (pinfunction "GND_4") (pintype "passive"))
      (node (ref "U4") (pin "4") (pinfunction "GND_4") (pintype "passive"))
      (node (ref "U5") (pin "11") (pinfunction "V-_11") (pintype "power_in"))
      (node (ref "U6") (pin "4") (pinfunction "GND_4") (pintype "passive"))
    )
    (net (code "27") (name "Net-(C40-Pad1)") (class "Default")
      (node (ref "C40") (pin "1") (pinfunction "1_1") (pintype "passive"))
      (node (ref "R52") (pin "2") (pinfunction "2_2") (pintype "passive"))
      (node (ref "R53") (pin "1") (pinfunction "1_1") (pintype "passive"))
    )
    (net (code "28") (name "Net-(C40-Pad2)") (class "Default")
      (node (ref "C40") (pin "2") (pinfunction "2_2") (pintype "passive"))
      (node (ref "R57") (pin "1") (pinfunction "1_1") (pintype "passive"))
      (node (ref "R59") (pin "2") (pinfunction "2_2") (pintype "passive"))
    )
    (net (code "29") (name "Net-(C42-Pad1)") (class "Default")
      (node (ref "C42") (pin "1") (pinfunction "1_1") (pintype "passive"))
      (node (ref "R63") (pin "2") (pinfunction "2_2") (pintype "passive"))
      (node (ref "R64") (pin "1") (pinfunction "1_1") (pintype "passive"))
    )
    (net (code "30") (name "Net-(C42-Pad2)") (class "Default")
      (node (ref "C42") (pin "2") (pinfunction "2_2") (pintype "passive"))
      (node (ref "R70") (pin "1") (pinfunction "1_1") (pintype "passive"))
      (node (ref "R72") (pin "2") (pinfunction "2_2") (pintype "passive"))
    )
    (net (code "31") (name "Net-(C43-Pad1)") (class "Default")
      (node (ref "C43") (pin "1") (pinfunction "1_1") (pintype "passive"))
      (node (ref "R65") (pin "2") (pinfunction "2_2") (pintype "passive"))
      (node (ref "R66") (pin "1") (pinfunction "1_1") (pintype "passive"))
    )
    (net (code "32") (name "Net-(C43-Pad2)") (class "Default")
      (node (ref "C43") (pin "2") (pinfunction "2_2") (pintype "passive"))
      (node (ref "R71") (pin "1") (pinfunction "1_1") (pintype "passive"))
      (node (ref "R73") (pin "2") (pinfunction "2_2") (pintype "passive"))
    )
    (net (code "33") (name "Net-(D6-A)") (class "Default")
      (node (ref "D6") (pin "1") (pinfunction "A_1") (pintype "passive"))
      (node (ref "R24") (pin "2") (pinfunction "2_2") (pintype "passive"))
    )
    (net (code "34") (name "Net-(D6-K)") (class "Default")
      (node (ref "C22") (pin "2") (pinfunction "2_2") (pintype "passive"))
      (node (ref "D6") (pin "2") (pinfunction "K_2") (pintype "passive"))
      (node (ref "U3") (pin "8") (pinfunction "VBOOT_8") (pintype "passive"))
    )
    (net (code "35") (name "Net-(D7-A)") (class "Default")
      (node (ref "D7") (pin "1") (pinfunction "A_1") (pintype "passive"))
      (node (ref "Q2") (pin "4") (pinfunction "G_4") (pintype "passive"))
      (node (ref "R25") (pin "2") (pinfunction "2_2") (pintype "passive"))
      (node (ref "R29") (pin "2") (pinfunction "2_2") (pintype "passive"))
    )
    (net (code "36") (name "Net-(D8-A)") (class "Default")
      (node (ref "D8") (pin "1") (pinfunction "A_1") (pintype "passive"))
      (node (ref "Q3") (pin "4") (pinfunction "G_4") (pintype "passive"))
      (node (ref "R26") (pin "2") (pinfunction "2_2") (pintype "passive"))
      (node (ref "R30") (pin "2") (pinfunction "2_2") (pintype "passive"))
    )
    (net (code "37") (name "Net-(D9-A)") (class "Default")
      (node (ref "D9") (pin "1") (pinfunction "A_1") (pintype "passive"))
      (node (ref "Q4") (pin "4") (pinfunction "G_4") (pintype "passive"))
      (node (ref "R27") (pin "2") (pinfunction "2_2") (pintype "passive"))
      (node (ref "R31") (pin "2") (pinfunction "2_2") (pintype "passive"))
    )
    (net (code "38") (name "Net-(D10-A)") (class "Default")
      (node (ref "D10") (pin "1") (pinfunction "A_1") (pintype "passive"))
      (node (ref "Q5") (pin "4") (pinfunction "G_4") (pintype "passive"))
      (node (ref "R33") (pin "2") (pinfunction "2_2") (pintype "passive"))
      (node (ref "R36") (pin "2") (pinfunction "2_2") (pintype "passive"))
    )
    (net (code "39") (name "Net-(D11-A)") (class "Default")
      (node (ref "D11") (pin "1") (pinfunction "A_1") (pintype "passive"))
      (node (ref "Q6") (pin "4") (pinfunction "G_4") (pintype "passive"))
      (node (ref "R34") (pin "2") (pinfunction "2_2") (pintype "passive"))
      (node (ref "R37") (pin "2") (pinfunction "2_2") (pintype "passive"))
    )
    (net (code "40") (name "Net-(D12-A)") (class "Default")
      (node (ref "D12") (pin "1") (pinfunction "A_1") (pintype "passive"))
      (node (ref "Q7") (pin "4") (pinfunction "G_4") (pintype "passive"))
      (node (ref "R35") (pin "2") (pinfunction "2_2") (pintype "passive"))
      (node (ref "R38") (pin "2") (pinfunction "2_2") (pintype "passive"))
    )
    (net (code "41") (name "Net-(D13-A)") (class "Default")
      (node (ref "D13") (pin "1") (pinfunction "A_1") (pintype "passive"))
      (node (ref "R41") (pin "2") (pinfunction "2_2") (pintype "passive"))
    )
    (net (code "42") (name "Net-(D13-K)") (class "Default")
      (node (ref "C31") (pin "2") (pinfunction "2_2") (pintype "passive"))
      (node (ref "D13") (pin "2") (pinfunction "K_2") (pintype "passive"))
      (node (ref "U4") (pin "8") (pinfunction "VBOOT_8") (pintype "passive"))
    )
    (net (code "43") (name "Net-(D14-A)") (class "Default")
      (node (ref "D14") (pin "1") (pinfunction "A_1") (pintype "passive"))
      (node (ref "R50") (pin "2") (pinfunction "2_2") (pintype "passive"))
    )
    (net (code "44") (name "Net-(D14-K)") (class "Default")
      (node (ref "C37") (pin "2") (pinfunction "2_2") (pintype "passive"))
      (node (ref "D14") (pin "2") (pinfunction "K_2") (pintype "passive"))
      (node (ref "U6") (pin "8") (pinfunction "VBOOT_8") (pintype "passive"))
    )
    (net (code "45") (name "Net-(R39-Pad1)") (class "Default")
      (node (ref "R39") (pin "1") (pinfunction "1_1") (pintype "passive"))
      (node (ref "R40") (pin "1") (pinfunction "1_1") (pintype "passive"))
      (node (ref "R42") (pin "1") (pinfunction "1_1") (pintype "passive"))
    )
    (net (code "46") (name "Net-(R54-Pad1)") (class "Default")
      (node (ref "R54") (pin "1") (pinfunction "1_1") (pintype "passive"))
      (node (ref "R56") (pin "2") (pinfunction "2_2") (pintype "passive"))
    )
    (net (code "47") (name "Net-(U3-IN_HI)") (class "Default")
      (node (ref "R28") (pin "2") (pinfunction "2_2") (pintype "passive"))
      (node (ref "U3") (pin "2") (pinfunction "IN_HI_2") (pintype "passive"))
    )
    (net (code "48") (name "Net-(U3-IN_LO)") (class "Default")
      (node (ref "R32") (pin "2") (pinfunction "2_2") (pintype "passive"))
      (node (ref "U3") (pin "3") (pinfunction "IN_LO_3") (pintype "passive"))
    )
    (net (code "49") (name "Net-(U4-IN_HI)") (class "Default")
      (node (ref "R46") (pin "2") (pinfunction "2_2") (pintype "passive"))
      (node (ref "U4") (pin "2") (pinfunction "IN_HI_2") (pintype "passive"))
    )
    (net (code "50") (name "Net-(U4-IN_LO)") (class "Default")
      (node (ref "R47") (pin "2") (pinfunction "2_2") (pintype "passive"))
      (node (ref "U4") (pin "3") (pinfunction "IN_LO_3") (pintype "passive"))
    )
    (net (code "51") (name "Net-(U5A-IN+)") (class "Default")
      (node (ref "C38") (pin "2") (pinfunction "2_2") (pintype "passive"))
      (node (ref "R49") (pin "2") (pinfunction "2_2") (pintype "passive"))
      (node (ref "R54") (pin "2") (pinfunction "2_2") (pintype "passive"))
      (node (ref "U5") (pin "3") (pinfunction "IN+_3") (pintype "input"))
    )
    (net (code "52") (name "Net-(U5A-IN-)") (class "Default")
      (node (ref "R48") (pin "2") (pinfunction "2_2") (pintype "passive"))
      (node (ref "U5") (pin "1") (pinfunction "OUT_1") (pintype "output"))
      (node (ref "U5") (pin "2") (pinfunction "IN-_2") (pintype "input"))
    )
    (net (code "53") (name "Net-(U5B-IN+)") (class "Default")
      (node (ref "R71") (pin "2") (pinfunction "2_2") (pintype "passive"))
      (node (ref "R75") (pin "2") (pinfunction "2_2") (pintype "passive"))
      (node (ref "U5") (pin "5") (pinfunction "IN+_5") (pintype "input"))
    )
    (net (code "54") (name "Net-(U5B-IN-)") (class "Default")
      (node (ref "R66") (pin "2") (pinfunction "2_2") (pintype "passive"))
      (node (ref "R67") (pin "1") (pinfunction "1_1") (pintype "passive"))
      (node (ref "U5") (pin "6") (pinfunction "IN-_6") (pintype "input"))
    )
    (net (code "55") (name "Net-(U5B-OUT)") (class "Default")
      (node (ref "R67") (pin "2") (pinfunction "2_2") (pintype "passive"))
      (node (ref "R69") (pin "2") (pinfunction "2_2") (pintype "passive"))
      (node (ref "U5") (pin "7") (pinfunction "OUT_7") (pintype "output"))
    )
    (net (code "56") (name "Net-(U5C-IN+)") (class "Default")
      (node (ref "R57") (pin "2") (pinfunction "2_2") (pintype "passive"))
      (node (ref "R61") (pin "2") (pinfunction "2_2") (pintype "passive"))
      (node (ref "U5") (pin "10") (pinfunction "IN+_10") (pintype "input"))
    )
    (net (code "57") (name "Net-(U5C-IN-)") (class "Default")
      (node (ref "R51") (pin "1") (pinfunction "1_1") (pintype "passive"))
      (node (ref "R53") (pin "2") (pinfunction "2_2") (pintype "passive"))
      (node (ref "U5") (pin "9") (pinfunction "IN-_9") (pintype "input"))
    )
    (net (code "58") (name "Net-(U5C-OUT)") (class "Default")
      (node (ref "R51") (pin "2") (pinfunction "2_2") (pintype "passive"))
      (node (ref "R55") (pin "2") (pinfunction "2_2") (pintype "passive"))
      (node (ref "U5") (pin "8") (pinfunction "OUT_8") (pintype "output"))
    )
    (net (code "59") (name "Net-(U5D-IN+)") (class "Default")
      (node (ref "R70") (pin "2") (pinfunction "2_2") (pintype "passive"))
      (node (ref "R74") (pin "2") (pinfunction "2_2") (pintype "passive"))
      (node (ref "U5") (pin "12") (pinfunction "IN+_12") (pintype "input"))
    )
    (net (code "60") (name "Net-(U5D-IN-)") (class "Default")
      (node (ref "R62") (pin "1") (pinfunction "1_1") (pintype "passive"))
      (node (ref "R64") (pin "2") (pinfunction "2_2") (pintype "passive"))
      (node (ref "U5") (pin "13") (pinfunction "IN-_13") (pintype "input"))
    )
    (net (code "61") (name "Net-(U5D-OUT)") (class "Default")
      (node (ref "R62") (pin "2") (pinfunction "2_2") (pintype "passive"))
      (node (ref "R68") (pin "2") (pinfunction "2_2") (pintype "passive"))
      (node (ref "U5") (pin "14") (pinfunction "OUT_14") (pintype "output"))
    )
    (net (code "62") (name "Net-(U6-IN_HI)") (class "Default")
      (node (ref "R58") (pin "2") (pinfunction "2_2") (pintype "passive"))
      (node (ref "U6") (pin "2") (pinfunction "IN_HI_2") (pintype "passive"))
    )
    (net (code "63") (name "Net-(U6-IN_LO)") (class "Default")
      (node (ref "R60") (pin "2") (pinfunction "2_2") (pintype "passive"))
      (node (ref "U6") (pin "3") (pinfunction "IN_LO_3") (pintype "passive"))
    )
    (net (code "64") (name "unconnected-(U5A-V+-Pad4)") (class "Default")
      (node (ref "U5") (pin "4") (pinfunction "V+_4") (pintype "power_in+no_connect"))
    )
    (net (code "65") (name "unconnected-(U5B-V+-Pad4)") (class "Default")
      (node (ref "U5") (pin "4") (pinfunction "V+_4") (pintype "power_in+no_connect"))
    )
    (net (code "66") (name "unconnected-(U5D-V+-Pad4)") (class "Default")
      (node (ref "U5") (pin "4") (pinfunction "V+_4") (pintype "power_in+no_connect"))
    )
  )
)
